# 5vdualsupply_sai.net
KiCad netlist of a schematic drawn in EAGLE
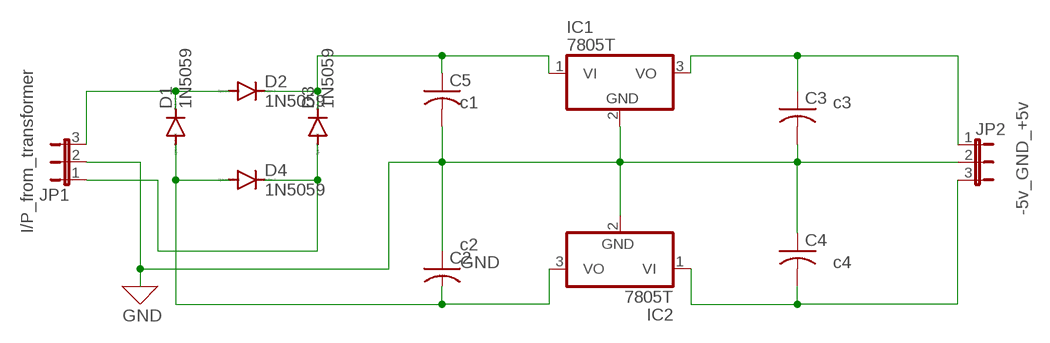
[diagram p0: schematic, sheet 1]

(export (version "E")
  (design (tool "Eeschema 10.0.6"))
  (components
    (comp (ref "C2")
      (value "C-US025-024X044")
      (footprint "eagle-import:C025-024X044")
      (libsource (lib "eagle-import") (part "C-US025-024X044"))
    )
    (comp (ref "C3")
      (value "C-US025-024X044")
      (footprint "eagle-import:C025-024X044")
      (libsource (lib "eagle-import") (part "C-US025-024X044"))
    )
    (comp (ref "C4")
      (value "C-US025-024X044")
      (footprint "eagle-import:C025-024X044")
      (libsource (lib "eagle-import") (part "C-US025-024X044"))
    )
    (comp (ref "C5")
      (value "C-US025-024X044")
      (footprint "eagle-import:C025-024X044")
      (libsource (lib "eagle-import") (part "C-US025-024X044"))
    )
    (comp (ref "D1")
      (value "1N5059")
      (footprint "eagle-import:DO204-10")
      (libsource (lib "eagle-import") (part "1N5059"))
    )
    (comp (ref "D2")
      (value "1N5059")
      (footprint "eagle-import:DO204-10")
      (libsource (lib "eagle-import") (part "1N5059"))
    )
    (comp (ref "D3")
      (value "1N5059")
      (footprint "eagle-import:DO204-10")
      (libsource (lib "eagle-import") (part "1N5059"))
    )
    (comp (ref "D4")
      (value "1N5059")
      (footprint "eagle-import:DO204-10")
      (libsource (lib "eagle-import") (part "1N5059"))
    )
    (comp (ref "IC1")
      (value "7805T")
      (footprint "eagle-import:TO220H")
      (libsource (lib "eagle-import") (part "78T05"))
    )
    (comp (ref "IC2")
      (value "7805T")
      (footprint "eagle-import:TO220H")
      (libsource (lib "eagle-import") (part "78T05"))
    )
    (comp (ref "JP1")
      (value "JP2W")
      (footprint "eagle-import:JP2W")
      (libsource (lib "eagle-import") (part "JP2W"))
    )
    (comp (ref "JP2")
      (value "JP2W")
      (footprint "eagle-import:JP2W")
      (libsource (lib "eagle-import") (part "JP2W"))
    )
  )
  (nets
    (net (code "1") (name "GND") (class "Default")
      (node (ref "C2") (pin "1") (pinfunction "1_1") (pintype "passive"))
      (node (ref "C3") (pin "2") (pinfunction "2_2") (pintype "passive"))
      (node (ref "C4") (pin "1") (pinfunction "1_1") (pintype "passive"))
      (node (ref "C5") (pin "2") (pinfunction "2_2") (pintype "passive"))
      (node (ref "IC1") (pin "2") (pinfunction "GND_2") (pintype "passive"))
      (node (ref "IC2") (pin "2") (pinfunction "GND_2") (pintype "passive"))
      (node (ref "JP1") (pin "2") (pinfunction "2_2") (pintype "passive"))
      (node (ref "JP2") (pin "2") (pinfunction "2_2") (pintype "passive"))
    )
    (net (code "2") (name "Net-(D1-PadC)") (class "Default")
      (node (ref "D1") (pin "C") (pinfunction "C_C") (pintype "passive"))
      (node (ref "D2") (pin "A") (pinfunction "A_A") (pintype "passive"))
      (node (ref "JP1") (pin "3") (pinfunction "3_3") (pintype "passive"))
    )
    (net (code "3") (name "Net-(D3-PadA)") (class "Default")
      (node (ref "D3") (pin "A") (pinfunction "A_A") (pintype "passive"))
      (node (ref "D4") (pin "C") (pinfunction "C_C") (pintype "passive"))
      (node (ref "JP1") (pin "1") (pinfunction "1_1") (pintype "passive"))
    )
    (net (code "4") (name "Net-(IC1-VI)") (class "Default")
      (node (ref "C5") (pin "1") (pinfunction "1_1") (pintype "passive"))
      (node (ref "D2") (pin "C") (pinfunction "C_C") (pintype "passive"))
      (node (ref "D3") (pin "C") (pinfunction "C_C") (pintype "passive"))
      (node (ref "IC1") (pin "1") (pinfunction "VI_1") (pintype "input"))
    )
    (net (code "5") (name "Net-(IC1-VO)") (class "Default")
      (node (ref "C3") (pin "1") (pinfunction "1_1") (pintype "passive"))
      (node (ref "IC1") (pin "3") (pinfunction "VO_3") (pintype "passive"))
      (node (ref "JP2") (pin "1") (pinfunction "1_1") (pintype "passive"))
    )
    (net (code "6") (name "Net-(IC2-VI)") (class "Default")
      (node (ref "C4") (pin "2") (pinfunction "2_2") (pintype "passive"))
      (node (ref "IC2") (pin "1") (pinfunction "VI_1") (pintype "input"))
      (node (ref "JP2") (pin "3") (pinfunction "3_3") (pintype "passive"))
    )
    (net (code "7") (name "Net-(IC2-VO)") (class "Default")
      (node (ref "C2") (pin "2") (pinfunction "2_2") (pintype "passive"))
      (node (ref "D1") (pin "A") (pinfunction "A_A") (pintype "passive"))
      (node (ref "D4") (pin "A") (pinfunction "A_A") (pintype "passive"))
      (node (ref "IC2") (pin "3") (pinfunction "VO_3") (pintype "passive"))
    )
  )
)
